# untitled.net
KiCad netlist of a schematic drawn in EAGLE
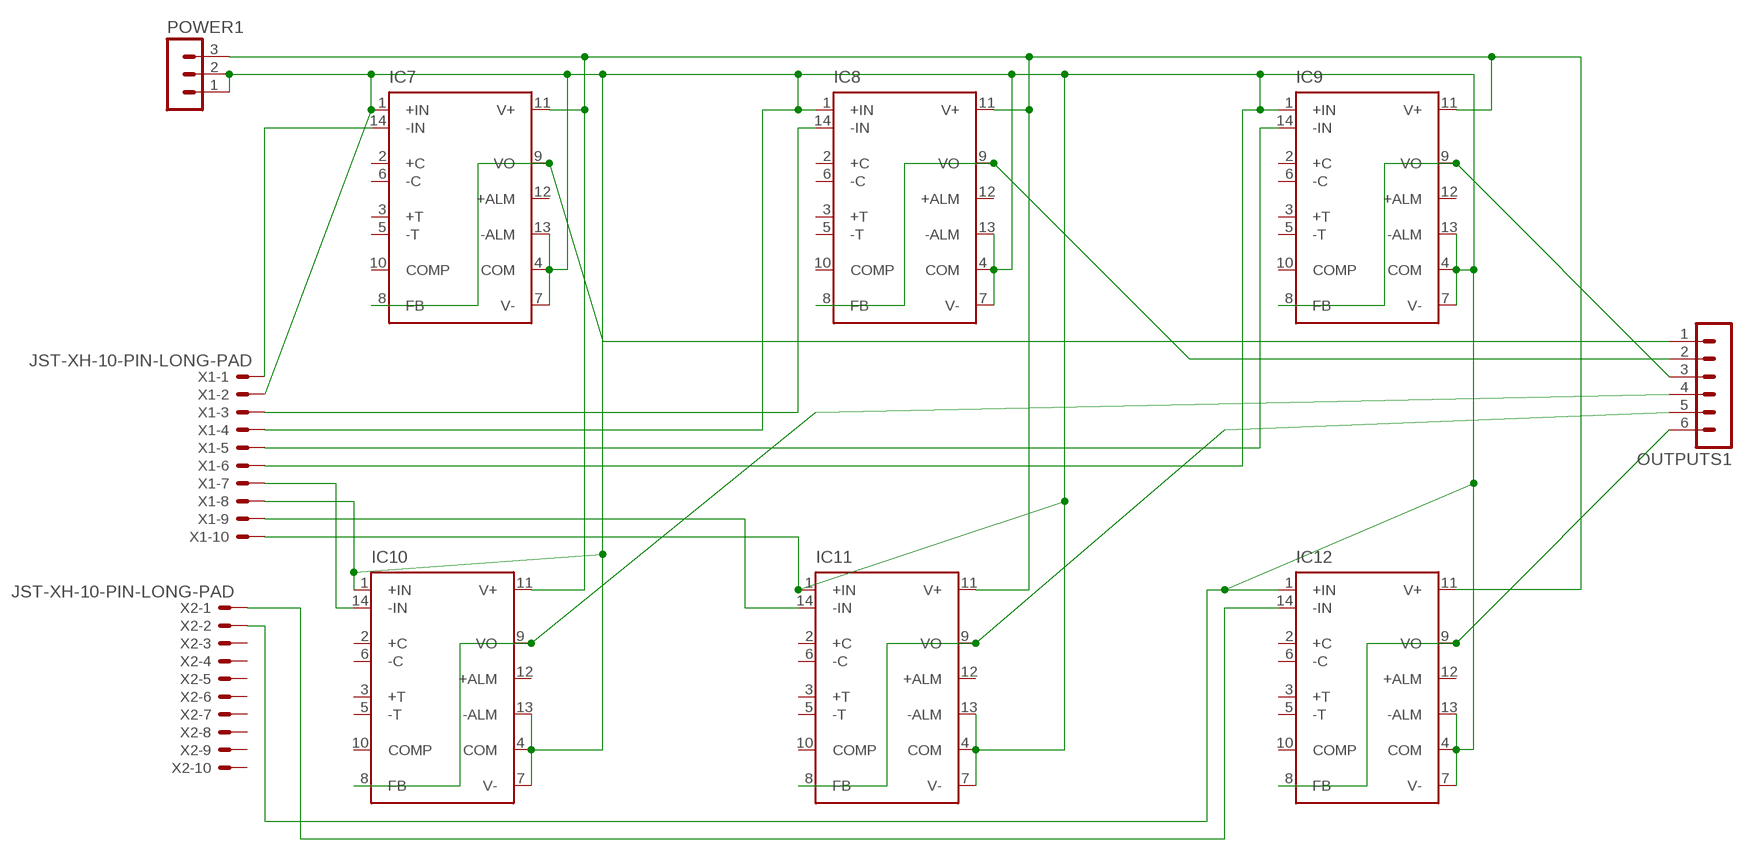
[diagram p0: schematic, sheet 1]

(export (version "E")
  (design (tool "Eeschema 10.0.6"))
  (components
    (comp (ref "IC7")
      (value "AD594")
      (footprint "eagle-import:DIL14")
      (fields (field (name "MF") "ALTERA CORPORATION") (field (name "MPN") "AD594AQ"))
      (libsource (lib "eagle-import") (part "AD594"))
    )
    (comp (ref "IC8")
      (value "AD594")
      (footprint "eagle-import:DIL14")
      (fields (field (name "MF") "ALTERA CORPORATION") (field (name "MPN") "AD594AQ"))
      (libsource (lib "eagle-import") (part "AD594"))
    )
    (comp (ref "IC9")
      (value "AD594")
      (footprint "eagle-import:DIL14")
      (fields (field (name "MF") "ALTERA CORPORATION") (field (name "MPN") "AD594AQ"))
      (libsource (lib "eagle-import") (part "AD594"))
    )
    (comp (ref "IC10")
      (value "AD594")
      (footprint "eagle-import:DIL14")
      (fields (field (name "MF") "ALTERA CORPORATION") (field (name "MPN") "AD594AQ"))
      (libsource (lib "eagle-import") (part "AD594"))
    )
    (comp (ref "IC11")
      (value "AD594")
      (footprint "eagle-import:DIL14")
      (fields (field (name "MF") "ALTERA CORPORATION") (field (name "MPN") "AD594AQ"))
      (libsource (lib "eagle-import") (part "AD594"))
    )
    (comp (ref "IC12")
      (value "AD594")
      (footprint "eagle-import:DIL14")
      (fields (field (name "MF") "ALTERA CORPORATION") (field (name "MPN") "AD594AQ"))
      (libsource (lib "eagle-import") (part "AD594"))
    )
    (comp (ref "OUTPUTS1")
      (value "MA06-1")
      (footprint "eagle-import:MA06-1")
      (libsource (lib "eagle-import") (part "MA06-1"))
    )
    (comp (ref "POWER1")
      (value "MA03-1")
      (footprint "eagle-import:MA03-1")
      (libsource (lib "eagle-import") (part "MA03-1"))
    )
    (comp (ref "X1")
      (value "JST-XH-10-PIN-LONG-PAD")
      (footprint "eagle-import:JST-XH-10-PACKAGE-LONG-PAD")
      (libsource (lib "eagle-import") (part "JST-XH-10-PIN-LONG-PAD"))
    )
    (comp (ref "X2")
      (value "JST-XH-10-PIN-LONG-PAD")
      (footprint "eagle-import:JST-XH-10-PACKAGE-LONG-PAD")
      (libsource (lib "eagle-import") (part "JST-XH-10-PIN-LONG-PAD"))
    )
  )
  (nets
    (net (code "1") (name "Net-(IC7--IN)") (class "Default")
      (node (ref "IC7") (pin "14") (pinfunction "-IN_14") (pintype "input"))
      (node (ref "X1") (pin "1") (pinfunction "S_1") (pintype "passive"))
    )
    (net (code "2") (name "Net-(IC7-FB)") (class "Default")
      (node (ref "IC7") (pin "8") (pinfunction "FB_8") (pintype "passive"))
      (node (ref "IC7") (pin "9") (pinfunction "VO_9") (pintype "output"))
      (node (ref "OUTPUTS1") (pin "1") (pinfunction "1_1") (pintype "passive"))
    )
    (net (code "3") (name "Net-(IC8--IN)") (class "Default")
      (node (ref "IC8") (pin "14") (pinfunction "-IN_14") (pintype "input"))
      (node (ref "X1") (pin "3") (pinfunction "S_3") (pintype "passive"))
    )
    (net (code "4") (name "Net-(IC8-FB)") (class "Default")
      (node (ref "IC8") (pin "8") (pinfunction "FB_8") (pintype "passive"))
      (node (ref "IC8") (pin "9") (pinfunction "VO_9") (pintype "output"))
      (node (ref "OUTPUTS1") (pin "2") (pinfunction "2_2") (pintype "passive"))
    )
    (net (code "5") (name "Net-(IC9--IN)") (class "Default")
      (node (ref "IC9") (pin "14") (pinfunction "-IN_14") (pintype "input"))
      (node (ref "X1") (pin "5") (pinfunction "S_5") (pintype "passive"))
    )
    (net (code "6") (name "Net-(IC9-FB)") (class "Default")
      (node (ref "IC9") (pin "8") (pinfunction "FB_8") (pintype "passive"))
      (node (ref "IC9") (pin "9") (pinfunction "VO_9") (pintype "output"))
      (node (ref "OUTPUTS1") (pin "3") (pinfunction "3_3") (pintype "passive"))
    )
    (net (code "7") (name "Net-(IC10-+IN)") (class "Default")
      (node (ref "IC10") (pin "1") (pinfunction "+IN_1") (pintype "input"))
      (node (ref "IC10") (pin "13") (pinfunction "-ALM_13") (pintype "passive"))
      (node (ref "IC10") (pin "4") (pinfunction "COM_4") (pintype "power_in"))
      (node (ref "IC10") (pin "7") (pinfunction "V-_7") (pintype "power_in"))
      (node (ref "IC11") (pin "1") (pinfunction "+IN_1") (pintype "input"))
      (node (ref "IC11") (pin "13") (pinfunction "-ALM_13") (pintype "passive"))
      (node (ref "IC11") (pin "4") (pinfunction "COM_4") (pintype "power_in"))
      (node (ref "IC11") (pin "7") (pinfunction "V-_7") (pintype "power_in"))
      (node (ref "IC12") (pin "1") (pinfunction "+IN_1") (pintype "input"))
      (node (ref "IC12") (pin "13") (pinfunction "-ALM_13") (pintype "passive"))
      (node (ref "IC12") (pin "4") (pinfunction "COM_4") (pintype "power_in"))
      (node (ref "IC12") (pin "7") (pinfunction "V-_7") (pintype "power_in"))
      (node (ref "IC7") (pin "1") (pinfunction "+IN_1") (pintype "input"))
      (node (ref "IC7") (pin "13") (pinfunction "-ALM_13") (pintype "passive"))
      (node (ref "IC7") (pin "4") (pinfunction "COM_4") (pintype "power_in"))
      (node (ref "IC7") (pin "7") (pinfunction "V-_7") (pintype "power_in"))
      (node (ref "IC8") (pin "1") (pinfunction "+IN_1") (pintype "input"))
      (node (ref "IC8") (pin "13") (pinfunction "-ALM_13") (pintype "passive"))
      (node (ref "IC8") (pin "4") (pinfunction "COM_4") (pintype "power_in"))
      (node (ref "IC8") (pin "7") (pinfunction "V-_7") (pintype "power_in"))
      (node (ref "IC9") (pin "1") (pinfunction "+IN_1") (pintype "input"))
      (node (ref "IC9") (pin "13") (pinfunction "-ALM_13") (pintype "passive"))
      (node (ref "IC9") (pin "4") (pinfunction "COM_4") (pintype "power_in"))
      (node (ref "IC9") (pin "7") (pinfunction "V-_7") (pintype "power_in"))
      (node (ref "POWER1") (pin "1") (pinfunction "1_1") (pintype "passive"))
      (node (ref "POWER1") (pin "2") (pinfunction "2_2") (pintype "passive"))
      (node (ref "X1") (pin "10") (pinfunction "S_10") (pintype "passive"))
      (node (ref "X1") (pin "2") (pinfunction "S_2") (pintype "passive"))
      (node (ref "X1") (pin "4") (pinfunction "S_4") (pintype "passive"))
      (node (ref "X1") (pin "6") (pinfunction "S_6") (pintype "passive"))
      (node (ref "X1") (pin "8") (pinfunction "S_8") (pintype "passive"))
      (node (ref "X2") (pin "2") (pinfunction "S_2") (pintype "passive"))
    )
    (net (code "8") (name "Net-(IC10--IN)") (class "Default")
      (node (ref "IC10") (pin "14") (pinfunction "-IN_14") (pintype "input"))
      (node (ref "X1") (pin "7") (pinfunction "S_7") (pintype "passive"))
    )
    (net (code "9") (name "Net-(IC10-FB)") (class "Default")
      (node (ref "IC10") (pin "8") (pinfunction "FB_8") (pintype "passive"))
      (node (ref "IC10") (pin "9") (pinfunction "VO_9") (pintype "output"))
      (node (ref "OUTPUTS1") (pin "4") (pinfunction "4_4") (pintype "passive"))
    )
    (net (code "10") (name "Net-(IC10-V+)") (class "Default")
      (node (ref "IC10") (pin "11") (pinfunction "V+_11") (pintype "power_in"))
      (node (ref "IC11") (pin "11") (pinfunction "V+_11") (pintype "power_in"))
      (node (ref "IC12") (pin "11") (pinfunction "V+_11") (pintype "power_in"))
      (node (ref "IC7") (pin "11") (pinfunction "V+_11") (pintype "power_in"))
      (node (ref "IC8") (pin "11") (pinfunction "V+_11") (pintype "power_in"))
      (node (ref "IC9") (pin "11") (pinfunction "V+_11") (pintype "power_in"))
      (node (ref "POWER1") (pin "3") (pinfunction "3_3") (pintype "passive"))
    )
    (net (code "11") (name "Net-(IC11--IN)") (class "Default")
      (node (ref "IC11") (pin "14") (pinfunction "-IN_14") (pintype "input"))
      (node (ref "X1") (pin "9") (pinfunction "S_9") (pintype "passive"))
    )
    (net (code "12") (name "Net-(IC11-FB)") (class "Default")
      (node (ref "IC11") (pin "8") (pinfunction "FB_8") (pintype "passive"))
      (node (ref "IC11") (pin "9") (pinfunction "VO_9") (pintype "output"))
      (node (ref "OUTPUTS1") (pin "5") (pinfunction "5_5") (pintype "passive"))
    )
    (net (code "13") (name "Net-(IC12--IN)") (class "Default")
      (node (ref "IC12") (pin "14") (pinfunction "-IN_14") (pintype "input"))
      (node (ref "X2") (pin "1") (pinfunction "S_1") (pintype "passive"))
    )
    (net (code "14") (name "Net-(IC12-FB)") (class "Default")
      (node (ref "IC12") (pin "8") (pinfunction "FB_8") (pintype "passive"))
      (node (ref "IC12") (pin "9") (pinfunction "VO_9") (pintype "output"))
      (node (ref "OUTPUTS1") (pin "6") (pinfunction "6_6") (pintype "passive"))
    )
    (net (code "15") (name "unconnected-(IC7-+ALM-Pad12)") (class "Default")
      (node (ref "IC7") (pin "12") (pinfunction "+ALM_12") (pintype "passive"))
    )
    (net (code "16") (name "unconnected-(IC7-+C-Pad2)") (class "Default")
      (node (ref "IC7") (pin "2") (pinfunction "+C_2") (pintype "input"))
    )
    (net (code "17") (name "unconnected-(IC7-+T-Pad3)") (class "Default")
      (node (ref "IC7") (pin "3") (pinfunction "+T_3") (pintype "passive"))
    )
    (net (code "18") (name "unconnected-(IC7--C-Pad6)") (class "Default")
      (node (ref "IC7") (pin "6") (pinfunction "-C_6") (pintype "input"))
    )
    (net (code "19") (name "unconnected-(IC7--T-Pad5)") (class "Default")
      (node (ref "IC7") (pin "5") (pinfunction "-T_5") (pintype "passive"))
    )
    (net (code "20") (name "unconnected-(IC7-COMP-Pad10)") (class "Default")
      (node (ref "IC7") (pin "10") (pinfunction "COMP_10") (pintype "passive"))
    )
    (net (code "21") (name "unconnected-(IC8-+ALM-Pad12)") (class "Default")
      (node (ref "IC8") (pin "12") (pinfunction "+ALM_12") (pintype "passive"))
    )
    (net (code "22") (name "unconnected-(IC8-+C-Pad2)") (class "Default")
      (node (ref "IC8") (pin "2") (pinfunction "+C_2") (pintype "input"))
    )
    (net (code "23") (name "unconnected-(IC8-+T-Pad3)") (class "Default")
      (node (ref "IC8") (pin "3") (pinfunction "+T_3") (pintype "passive"))
    )
    (net (code "24") (name "unconnected-(IC8--C-Pad6)") (class "Default")
      (node (ref "IC8") (pin "6") (pinfunction "-C_6") (pintype "input"))
    )
    (net (code "25") (name "unconnected-(IC8--T-Pad5)") (class "Default")
      (node (ref "IC8") (pin "5") (pinfunction "-T_5") (pintype "passive"))
    )
    (net (code "26") (name "unconnected-(IC8-COMP-Pad10)") (class "Default")
      (node (ref "IC8") (pin "10") (pinfunction "COMP_10") (pintype "passive"))
    )
    (net (code "27") (name "unconnected-(IC9-+ALM-Pad12)") (class "Default")
      (node (ref "IC9") (pin "12") (pinfunction "+ALM_12") (pintype "passive"))
    )
    (net (code "28") (name "unconnected-(IC9-+C-Pad2)") (class "Default")
      (node (ref "IC9") (pin "2") (pinfunction "+C_2") (pintype "input"))
    )
    (net (code "29") (name "unconnected-(IC9-+T-Pad3)") (class "Default")
      (node (ref "IC9") (pin "3") (pinfunction "+T_3") (pintype "passive"))
    )
    (net (code "30") (name "unconnected-(IC9--C-Pad6)") (class "Default")
      (node (ref "IC9") (pin "6") (pinfunction "-C_6") (pintype "input"))
    )
    (net (code "31") (name "unconnected-(IC9--T-Pad5)") (class "Default")
      (node (ref "IC9") (pin "5") (pinfunction "-T_5") (pintype "passive"))
    )
    (net (code "32") (name "unconnected-(IC9-COMP-Pad10)") (class "Default")
      (node (ref "IC9") (pin "10") (pinfunction "COMP_10") (pintype "passive"))
    )
    (net (code "33") (name "unconnected-(IC10-+ALM-Pad12)") (class "Default")
      (node (ref "IC10") (pin "12") (pinfunction "+ALM_12") (pintype "passive"))
    )
    (net (code "34") (name "unconnected-(IC10-+C-Pad2)") (class "Default")
      (node (ref "IC10") (pin "2") (pinfunction "+C_2") (pintype "input"))
    )
    (net (code "35") (name "unconnected-(IC10-+T-Pad3)") (class "Default")
      (node (ref "IC10") (pin "3") (pinfunction "+T_3") (pintype "passive"))
    )
    (net (code "36") (name "unconnected-(IC10--C-Pad6)") (class "Default")
      (node (ref "IC10") (pin "6") (pinfunction "-C_6") (pintype "input"))
    )
    (net (code "37") (name "unconnected-(IC10--T-Pad5)") (class "Default")
      (node (ref "IC10") (pin "5") (pinfunction "-T_5") (pintype "passive"))
    )
    (net (code "38") (name "unconnected-(IC10-COMP-Pad10)") (class "Default")
      (node (ref "IC10") (pin "10") (pinfunction "COMP_10") (pintype "passive"))
    )
    (net (code "39") (name "unconnected-(IC11-+ALM-Pad12)") (class "Default")
      (node (ref "IC11") (pin "12") (pinfunction "+ALM_12") (pintype "passive"))
    )
    (net (code "40") (name "unconnected-(IC11-+C-Pad2)") (class "Default")
      (node (ref "IC11") (pin "2") (pinfunction "+C_2") (pintype "input"))
    )
    (net (code "41") (name "unconnected-(IC11-+T-Pad3)") (class "Default")
      (node (ref "IC11") (pin "3") (pinfunction "+T_3") (pintype "passive"))
    )
    (net (code "42") (name "unconnected-(IC11--C-Pad6)") (class "Default")
      (node (ref "IC11") (pin "6") (pinfunction "-C_6") (pintype "input"))
    )
    (net (code "43") (name "unconnected-(IC11--T-Pad5)") (class "Default")
      (node (ref "IC11") (pin "5") (pinfunction "-T_5") (pintype "passive"))
    )
    (net (code "44") (name "unconnected-(IC11-COMP-Pad10)") (class "Default")
      (node (ref "IC11") (pin "10") (pinfunction "COMP_10") (pintype "passive"))
    )
    (net (code "45") (name "unconnected-(IC12-+ALM-Pad12)") (class "Default")
      (node (ref "IC12") (pin "12") (pinfunction "+ALM_12") (pintype "passive"))
    )
    (net (code "46") (name "unconnected-(IC12-+C-Pad2)") (class "Default")
      (node (ref "IC12") (pin "2") (pinfunction "+C_2") (pintype "input"))
    )
    (net (code "47") (name "unconnected-(IC12-+T-Pad3)") (class "Default")
      (node (ref "IC12") (pin "3") (pinfunction "+T_3") (pintype "passive"))
    )
    (net (code "48") (name "unconnected-(IC12--C-Pad6)") (class "Default")
      (node (ref "IC12") (pin "6") (pinfunction "-C_6") (pintype "input"))
    )
    (net (code "49") (name "unconnected-(IC12--T-Pad5)") (class "Default")
      (node (ref "IC12") (pin "5") (pinfunction "-T_5") (pintype "passive"))
    )
    (net (code "50") (name "unconnected-(IC12-COMP-Pad10)") (class "Default")
      (node (ref "IC12") (pin "10") (pinfunction "COMP_10") (pintype "passive"))
    )
    (net (code "51") (name "unconnected-(X2B-S-Pad10)") (class "Default")
      (node (ref "X2") (pin "10") (pinfunction "S_10") (pintype "passive"))
    )
    (net (code "52") (name "unconnected-(X2D-S-Pad3)") (class "Default")
      (node (ref "X2") (pin "3") (pinfunction "S_3") (pintype "passive"))
    )
    (net (code "53") (name "unconnected-(X2E-S-Pad4)") (class "Default")
      (node (ref "X2") (pin "4") (pinfunction "S_4") (pintype "passive"))
    )
    (net (code "54") (name "unconnected-(X2F-S-Pad5)") (class "Default")
      (node (ref "X2") (pin "5") (pinfunction "S_5") (pintype "passive"))
    )
    (net (code "55") (name "unconnected-(X2G-S-Pad6)") (class "Default")
      (node (ref "X2") (pin "6") (pinfunction "S_6") (pintype "passive"))
    )
    (net (code "56") (name "unconnected-(X2H-S-Pad7)") (class "Default")
      (node (ref "X2") (pin "7") (pinfunction "S_7") (pintype "passive"))
    )
    (net (code "57") (name "unconnected-(X2I-S-Pad8)") (class "Default")
      (node (ref "X2") (pin "8") (pinfunction "S_8") (pintype "passive"))
    )
    (net (code "58") (name "unconnected-(X2J-S-Pad9)") (class "Default")
      (node (ref "X2") (pin "9") (pinfunction "S_9") (pintype "passive"))
    )
  )
)
